# LIS2.net
KiCad netlist of a schematic drawn in Altium Designer
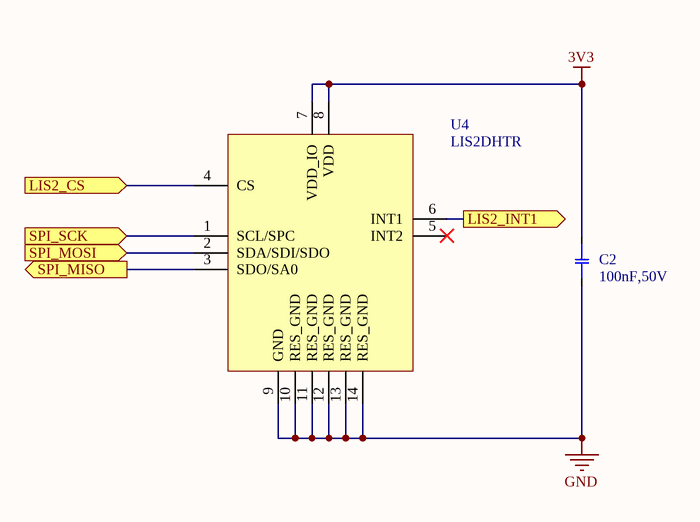
[diagram p0: LIS2.SchDoc]

(export (version "E")
  (design (tool "Eeschema 10.0.6"))
  (components
    (comp (ref "C2")
      (value "100nF,50V")
      (footprint "CAPC1608X09N_0603")
      (description "CAP CER 0.1UF 50V 10% X7R 0603")
      (fields (field (name "MANUFACTURER") "Kemet") (field (name "TOLERANCE") "10%"))
      (libsource (lib "library") (part "CAP-NP_1"))
    )
    (comp (ref "U4")
      (value "LIS2DHTR")
      (footprint "PQFN35P200X200X100-14N")
      (description "IC ACCELEROMETER I2C/SPI 14-LGA")
      (fields (field (name "MANUFACTURER") "STMicroelectronics"))
      (libsource (lib "library") (part "LIS2DHTR"))
    )
  )
  (nets
    (net (code "1") (name "/LIS2_CS") (class "Default")
      (node (ref "U4") (pin "4") (pinfunction "CS_4") (pintype "passive"))
    )
    (net (code "2") (name "/LIS2_INT1") (class "Default")
      (node (ref "U4") (pin "6") (pinfunction "INT1_6") (pintype "passive"))
    )
    (net (code "3") (name "/SPI_MISO") (class "Default")
      (node (ref "U4") (pin "3") (pinfunction "SDO/SA0_3") (pintype "passive"))
    )
    (net (code "4") (name "/SPI_MOSI") (class "Default")
      (node (ref "U4") (pin "2") (pinfunction "SDA/SDI/SDO_2") (pintype "passive"))
    )
    (net (code "5") (name "/SPI_SCK") (class "Default")
      (node (ref "U4") (pin "1") (pinfunction "SCL/SPC_1") (pintype "passive"))
    )
    (net (code "6") (name "3V3") (class "Default")
      (node (ref "C2") (pin "2") (pinfunction "2_2") (pintype "passive"))
      (node (ref "U4") (pin "7") (pinfunction "VDD_IO_7") (pintype "passive"))
      (node (ref "U4") (pin "8") (pinfunction "VDD_8") (pintype "passive"))
    )
    (net (code "7") (name "GND") (class "Default")
      (node (ref "C2") (pin "1") (pinfunction "1_1") (pintype "passive"))
      (node (ref "U4") (pin "10") (pinfunction "RES_GND_10") (pintype "passive"))
      (node (ref "U4") (pin "11") (pinfunction "RES_GND_11") (pintype "passive"))
      (node (ref "U4") (pin "12") (pinfunction "RES_GND_12") (pintype "passive"))
      (node (ref "U4") (pin "13") (pinfunction "RES_GND_13") (pintype "passive"))
      (node (ref "U4") (pin "14") (pinfunction "RES_GND_14") (pintype "passive"))
      (node (ref "U4") (pin "9") (pinfunction "GND_9") (pintype "passive"))
    )
    (net (code "8") (name "unconnected-(U4-INT2-Pad5)") (class "Default")
      (node (ref "U4") (pin "5") (pinfunction "INT2_5") (pintype "passive+no_connect"))
    )
  )
)
